# 11-CPU_GPIO.net
KiCad netlist of a schematic drawn in Altium Designer
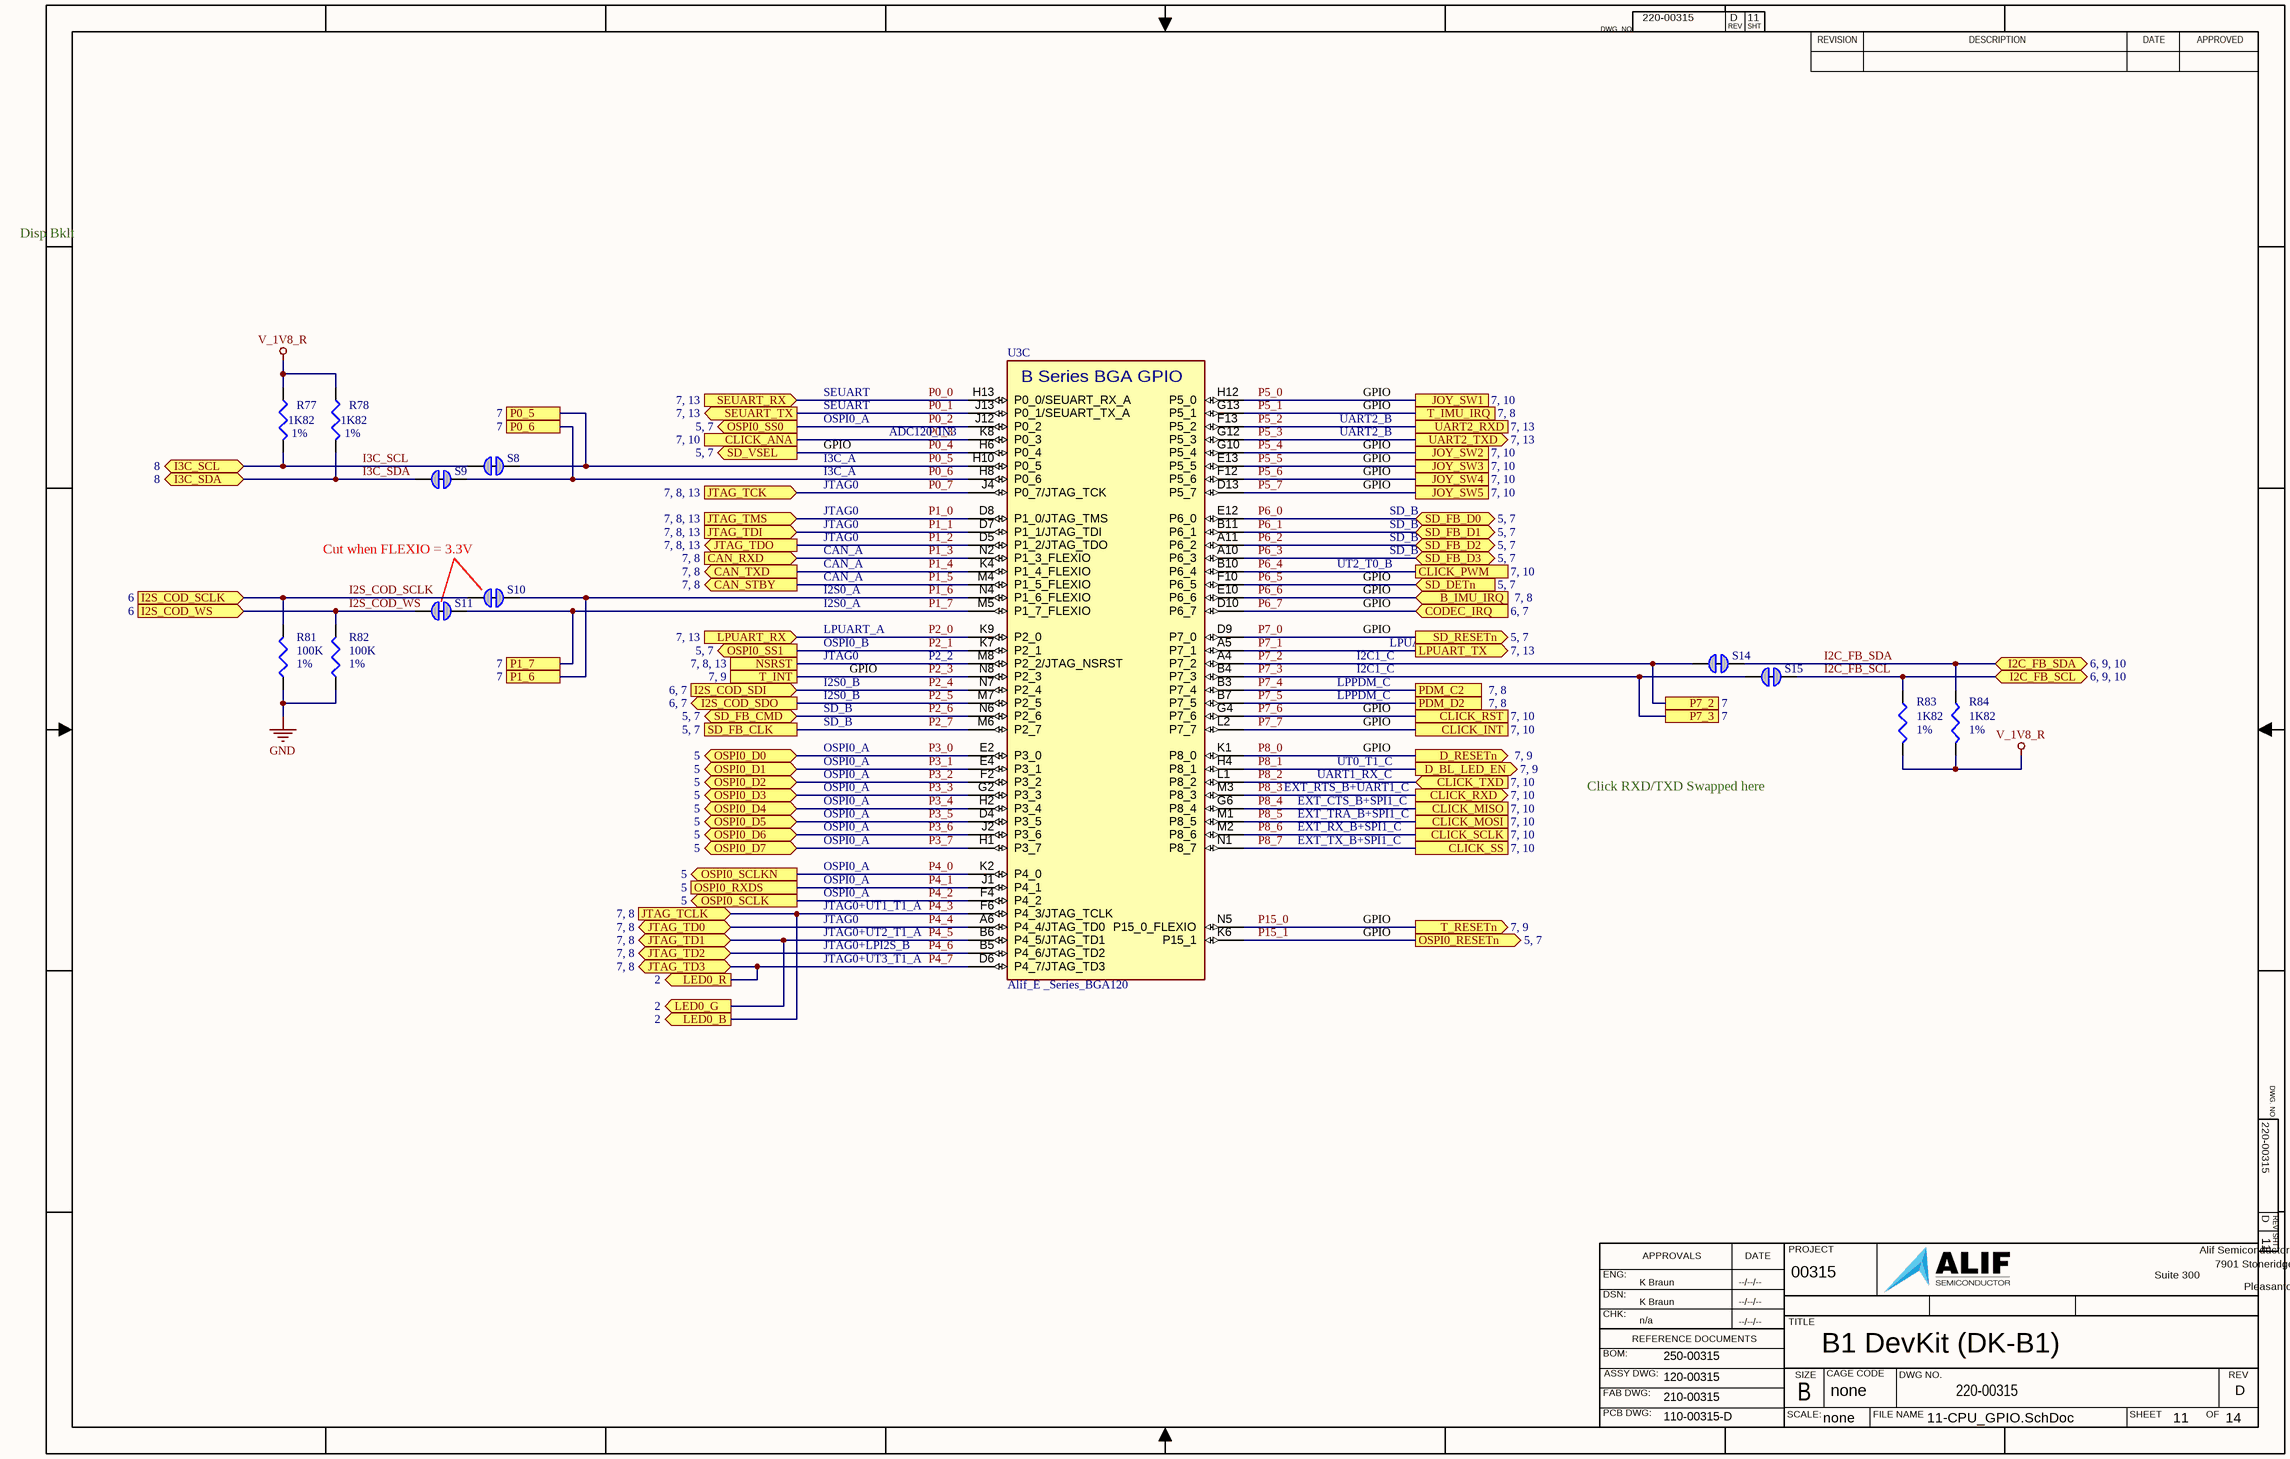
[diagram p0: 11-CPU_GPIO.SchDoc]

(export (version "E")
  (design (tool "Eeschema 10.0.6"))
  (components
    (comp (ref "R77")
      (value "1K82")
      (footprint "RESC0402-01")
      (description "Res,1K82,1%,100ppm,0402")
      (fields
        (field (name "TOLERANCE") "1%")
        (field (name "Comment") "Res3")
        (field (name "PUBLISHER") "Altium Limited")
      )
      (libsource (lib "kb1") (part "Res3"))
    )
    (comp (ref "R78")
      (value "1K82")
      (footprint "RESC0402-01")
      (description "Res,1K82,1%,100ppm,0402")
      (fields
        (field (name "TOLERANCE") "1%")
        (field (name "Comment") "Res3")
        (field (name "PUBLISHER") "Altium Limited")
      )
      (libsource (lib "kb1") (part "Res3"))
    )
    (comp (ref "R81")
      (value "100K")
      (footprint "RESC0402-01")
      (description "Res,100K,1%,100ppm,0402")
      (fields
        (field (name "TOLERANCE") "1%")
        (field (name "Comment") "Res3")
        (field (name "PUBLISHER") "Altium Limited")
      )
      (libsource (lib "kb1") (part "Res3"))
    )
    (comp (ref "R82")
      (value "100K")
      (footprint "RESC0402-01")
      (description "Res,100K,1%,100ppm,0402")
      (fields
        (field (name "TOLERANCE") "1%")
        (field (name "Comment") "Res3")
        (field (name "PUBLISHER") "Altium Limited")
      )
      (libsource (lib "kb1") (part "Res3"))
    )
    (comp (ref "R83")
      (value "1K82")
      (footprint "RESC0402-01")
      (description "Res,1K82,1%,100ppm,0402")
      (fields
        (field (name "TOLERANCE") "1%")
        (field (name "Comment") "Res3")
        (field (name "PUBLISHER") "Altium Limited")
      )
      (libsource (lib "kb1") (part "Res3"))
    )
    (comp (ref "R84")
      (value "1K82")
      (footprint "RESC0402-01")
      (description "Res,1K82,1%,100ppm,0402")
      (fields
        (field (name "TOLERANCE") "1%")
        (field (name "Comment") "Res3")
        (field (name "PUBLISHER") "Altium Limited")
      )
      (libsource (lib "kb1") (part "Res3"))
    )
    (comp (ref "S8")
      (value "SolderJumperShorted_Small")
      (footprint "Solderbridge_Shorted")
      (description "DNI,Solderable Jumper,Shorted")
      (fields (field (name "PUBLISHER") "Altium Limited"))
      (libsource (lib "Alif-2") (part "SolderJumperShorted_Small"))
    )
    (comp (ref "S9")
      (value "SolderJumperShorted_Small")
      (footprint "Solderbridge_Shorted")
      (description "DNI,Solderable Jumper,Shorted")
      (fields (field (name "PUBLISHER") "Altium Limited"))
      (libsource (lib "Alif-2") (part "SolderJumperShorted_Small"))
    )
    (comp (ref "S10")
      (value "SolderJumperShorted_Small")
      (footprint "Solderbridge_Shorted")
      (description "DNI,Solderable Jumper,Shorted")
      (fields (field (name "PUBLISHER") "Altium Limited"))
      (libsource (lib "Alif-2") (part "SolderJumperShorted_Small"))
    )
    (comp (ref "S11")
      (value "SolderJumperShorted_Small")
      (footprint "Solderbridge_Shorted")
      (description "DNI,Solderable Jumper,Shorted")
      (fields (field (name "PUBLISHER") "Altium Limited"))
      (libsource (lib "Alif-2") (part "SolderJumperShorted_Small"))
    )
    (comp (ref "S14")
      (value "SolderJumperShorted_Small")
      (footprint "Solderbridge_Shorted")
      (description "DNI,Solderable Jumper,Shorted")
      (fields (field (name "PUBLISHER") "Altium Limited"))
      (libsource (lib "") (part "SolderJumperShorted_Small_1"))
    )
    (comp (ref "S15")
      (value "SolderJumperShorted_Small")
      (footprint "Solderbridge_Shorted")
      (description "DNI,Solderable Jumper,Shorted")
      (fields (field (name "PUBLISHER") "Altium Limited"))
      (libsource (lib "") (part "SolderJumperShorted_Small_1"))
    )
    (comp (ref "U3")
      (value "Alif_E _Series_BGA120")
      (footprint "BGA120_socket-NO_SOCK_3D")
      (description "IC,Alif Spark B1 MCU, Rev A5 silicon,BGA120")
      (libsource (lib "Alif") (part "SPARK_B1_120BGA_A5"))
    )
  )
  (nets
    (net (code "1") (name "/I2C_FB_SCL") (class "Default")
      (node (ref "R83") (pin "1") (pinfunction "1_1") (pintype "passive"))
      (node (ref "S15") (pin "1") (pinfunction "1_1") (pintype "passive"))
    )
    (net (code "2") (name "/I2C_FB_SDA") (class "Default")
      (node (ref "R84") (pin "1") (pinfunction "1_1") (pintype "passive"))
      (node (ref "S14") (pin "1") (pinfunction "1_1") (pintype "passive"))
    )
    (net (code "3") (name "/I2S_COD_SCLK") (class "Default")
      (node (ref "R81") (pin "2") (pinfunction "2_2") (pintype "passive"))
      (node (ref "S10") (pin "1") (pinfunction "1_1") (pintype "passive"))
    )
    (net (code "4") (name "/I2S_COD_WS") (class "Default")
      (node (ref "R82") (pin "2") (pinfunction "2_2") (pintype "passive"))
      (node (ref "S11") (pin "1") (pinfunction "1_1") (pintype "passive"))
    )
    (net (code "5") (name "/I3C_SCL") (class "Default")
      (node (ref "R77") (pin "1") (pinfunction "1_1") (pintype "passive"))
      (node (ref "S8") (pin "1") (pinfunction "1_1") (pintype "passive"))
    )
    (net (code "6") (name "/I3C_SDA") (class "Default")
      (node (ref "R78") (pin "1") (pinfunction "1_1") (pintype "passive"))
      (node (ref "S9") (pin "1") (pinfunction "1_1") (pintype "passive"))
    )
    (net (code "7") (name "/NSRST") (class "Default")
      (node (ref "U3") (pin "M8") (pinfunction "P2_2/JTAG_NSRST_M8") (pintype "bidirectional"))
    )
    (net (code "8") (name "/P0_0") (class "Default")
      (node (ref "U3") (pin "H13") (pinfunction "P0_0/SEUART_RX_A_H13") (pintype "bidirectional"))
    )
    (net (code "9") (name "/P0_1") (class "Default")
      (node (ref "U3") (pin "J13") (pinfunction "P0_1/SEUART_TX_A_J13") (pintype "bidirectional"))
    )
    (net (code "10") (name "/P0_2") (class "Default")
      (node (ref "U3") (pin "J12") (pinfunction "P0_2_J12") (pintype "bidirectional"))
    )
    (net (code "11") (name "/P0_3") (class "Default")
      (node (ref "U3") (pin "K8") (pinfunction "P0_3_K8") (pintype "bidirectional"))
    )
    (net (code "12") (name "/P0_4") (class "Default")
      (node (ref "U3") (pin "H6") (pinfunction "P0_4_H6") (pintype "bidirectional"))
    )
    (net (code "13") (name "/P0_5") (class "Default")
      (node (ref "S8") (pin "2") (pinfunction "2_2") (pintype "passive"))
      (node (ref "U3") (pin "H10") (pinfunction "P0_5_H10") (pintype "bidirectional"))
    )
    (net (code "14") (name "/P0_6") (class "Default")
      (node (ref "S9") (pin "2") (pinfunction "2_2") (pintype "passive"))
      (node (ref "U3") (pin "H8") (pinfunction "P0_6_H8") (pintype "bidirectional"))
    )
    (net (code "15") (name "/P0_7") (class "Default")
      (node (ref "U3") (pin "J4") (pinfunction "P0_7/JTAG_TCK_J4") (pintype "bidirectional"))
    )
    (net (code "16") (name "/P1_0") (class "Default")
      (node (ref "U3") (pin "D8") (pinfunction "P1_0/JTAG_TMS_D8") (pintype "bidirectional"))
    )
    (net (code "17") (name "/P1_1") (class "Default")
      (node (ref "U3") (pin "D7") (pinfunction "P1_1/JTAG_TDI_D7") (pintype "bidirectional"))
    )
    (net (code "18") (name "/P1_2") (class "Default")
      (node (ref "U3") (pin "D5") (pinfunction "P1_2/JTAG_TDO_D5") (pintype "bidirectional"))
    )
    (net (code "19") (name "/P1_3") (class "Default")
      (node (ref "U3") (pin "N2") (pinfunction "P1_3_FLEXIO_N2") (pintype "bidirectional"))
    )
    (net (code "20") (name "/P1_4") (class "Default")
      (node (ref "U3") (pin "K4") (pinfunction "P1_4_FLEXIO_K4") (pintype "bidirectional"))
    )
    (net (code "21") (name "/P1_5") (class "Default")
      (node (ref "U3") (pin "M4") (pinfunction "P1_5_FLEXIO_M4") (pintype "bidirectional"))
    )
    (net (code "22") (name "/P1_6") (class "Default")
      (node (ref "S10") (pin "2") (pinfunction "2_2") (pintype "passive"))
      (node (ref "U3") (pin "N4") (pinfunction "P1_6_FLEXIO_N4") (pintype "bidirectional"))
    )
    (net (code "23") (name "/P1_7") (class "Default")
      (node (ref "S11") (pin "2") (pinfunction "2_2") (pintype "passive"))
      (node (ref "U3") (pin "M5") (pinfunction "P1_7_FLEXIO_M5") (pintype "bidirectional"))
    )
    (net (code "24") (name "/P2_0") (class "Default")
      (node (ref "U3") (pin "K9") (pinfunction "P2_0_K9") (pintype "bidirectional"))
    )
    (net (code "25") (name "/P2_1") (class "Default")
      (node (ref "U3") (pin "K7") (pinfunction "P2_1_K7") (pintype "bidirectional"))
    )
    (net (code "26") (name "/P2_3") (class "Default")
      (node (ref "U3") (pin "N8") (pinfunction "P2_3_N8") (pintype "bidirectional"))
    )
    (net (code "27") (name "/P2_4") (class "Default")
      (node (ref "U3") (pin "N7") (pinfunction "P2_4_N7") (pintype "bidirectional"))
    )
    (net (code "28") (name "/P2_5") (class "Default")
      (node (ref "U3") (pin "M7") (pinfunction "P2_5_M7") (pintype "bidirectional"))
    )
    (net (code "29") (name "/P2_6") (class "Default")
      (node (ref "U3") (pin "N6") (pinfunction "P2_6_N6") (pintype "bidirectional"))
    )
    (net (code "30") (name "/P2_7") (class "Default")
      (node (ref "U3") (pin "M6") (pinfunction "P2_7_M6") (pintype "bidirectional"))
    )
    (net (code "31") (name "/P3_0") (class "Default")
      (node (ref "U3") (pin "E2") (pinfunction "P3_0_E2") (pintype "bidirectional"))
    )
    (net (code "32") (name "/P3_1") (class "Default")
      (node (ref "U3") (pin "E4") (pinfunction "P3_1_E4") (pintype "bidirectional"))
    )
    (net (code "33") (name "/P3_2") (class "Default")
      (node (ref "U3") (pin "F2") (pinfunction "P3_2_F2") (pintype "bidirectional"))
    )
    (net (code "34") (name "/P3_3") (class "Default")
      (node (ref "U3") (pin "G2") (pinfunction "P3_3_G2") (pintype "bidirectional"))
    )
    (net (code "35") (name "/P3_4") (class "Default")
      (node (ref "U3") (pin "H2") (pinfunction "P3_4_H2") (pintype "bidirectional"))
    )
    (net (code "36") (name "/P3_5") (class "Default")
      (node (ref "U3") (pin "D4") (pinfunction "P3_5_D4") (pintype "bidirectional"))
    )
    (net (code "37") (name "/P3_6") (class "Default")
      (node (ref "U3") (pin "J2") (pinfunction "P3_6_J2") (pintype "bidirectional"))
    )
    (net (code "38") (name "/P3_7") (class "Default")
      (node (ref "U3") (pin "H1") (pinfunction "P3_7_H1") (pintype "bidirectional"))
    )
    (net (code "39") (name "/P4_0") (class "Default")
      (node (ref "U3") (pin "K2") (pinfunction "P4_0_K2") (pintype "bidirectional"))
    )
    (net (code "40") (name "/P4_1") (class "Default")
      (node (ref "U3") (pin "J1") (pinfunction "P4_1_J1") (pintype "bidirectional"))
    )
    (net (code "41") (name "/P4_2") (class "Default")
      (node (ref "U3") (pin "F4") (pinfunction "P4_2_F4") (pintype "bidirectional"))
    )
    (net (code "42") (name "/P4_3") (class "Default")
      (node (ref "U3") (pin "F6") (pinfunction "P4_3/JTAG_TCLK_F6") (pintype "bidirectional"))
    )
    (net (code "43") (name "/P4_4") (class "Default")
      (node (ref "U3") (pin "A6") (pinfunction "P4_4/JTAG_TD0_A6") (pintype "bidirectional"))
    )
    (net (code "44") (name "/P4_5") (class "Default")
      (node (ref "U3") (pin "B6") (pinfunction "P4_5/JTAG_TD1_B6") (pintype "bidirectional"))
    )
    (net (code "45") (name "/P4_6") (class "Default")
      (node (ref "U3") (pin "B5") (pinfunction "P4_6/JTAG_TD2_B5") (pintype "bidirectional"))
    )
    (net (code "46") (name "/P4_7") (class "Default")
      (node (ref "U3") (pin "D6") (pinfunction "P4_7/JTAG_TD3_D6") (pintype "bidirectional"))
    )
    (net (code "47") (name "/P5_0") (class "Default")
      (node (ref "U3") (pin "H12") (pinfunction "P5_0_H12") (pintype "bidirectional"))
    )
    (net (code "48") (name "/P5_1") (class "Default")
      (node (ref "U3") (pin "G13") (pinfunction "P5_1_G13") (pintype "bidirectional"))
    )
    (net (code "49") (name "/P5_2") (class "Default")
      (node (ref "U3") (pin "F13") (pinfunction "P5_2_F13") (pintype "bidirectional"))
    )
    (net (code "50") (name "/P5_3") (class "Default")
      (node (ref "U3") (pin "G12") (pinfunction "P5_3_G12") (pintype "bidirectional"))
    )
    (net (code "51") (name "/P5_4") (class "Default")
      (node (ref "U3") (pin "G10") (pinfunction "P5_4_G10") (pintype "bidirectional"))
    )
    (net (code "52") (name "/P5_5") (class "Default")
      (node (ref "U3") (pin "E13") (pinfunction "P5_5_E13") (pintype "bidirectional"))
    )
    (net (code "53") (name "/P5_6") (class "Default")
      (node (ref "U3") (pin "F12") (pinfunction "P5_6_F12") (pintype "bidirectional"))
    )
    (net (code "54") (name "/P5_7") (class "Default")
      (node (ref "U3") (pin "D13") (pinfunction "P5_7_D13") (pintype "bidirectional"))
    )
    (net (code "55") (name "/P6_0") (class "Default")
      (node (ref "U3") (pin "E12") (pinfunction "P6_0_E12") (pintype "bidirectional"))
    )
    (net (code "56") (name "/P6_1") (class "Default")
      (node (ref "U3") (pin "B11") (pinfunction "P6_1_B11") (pintype "bidirectional"))
    )
    (net (code "57") (name "/P6_2") (class "Default")
      (node (ref "U3") (pin "A11") (pinfunction "P6_2_A11") (pintype "bidirectional"))
    )
    (net (code "58") (name "/P6_3") (class "Default")
      (node (ref "U3") (pin "A10") (pinfunction "P6_3_A10") (pintype "bidirectional"))
    )
    (net (code "59") (name "/P6_4") (class "Default")
      (node (ref "U3") (pin "B10") (pinfunction "P6_4_B10") (pintype "bidirectional"))
    )
    (net (code "60") (name "/P6_5") (class "Default")
      (node (ref "U3") (pin "F10") (pinfunction "P6_5_F10") (pintype "bidirectional"))
    )
    (net (code "61") (name "/P6_6") (class "Default")
      (node (ref "U3") (pin "E10") (pinfunction "P6_6_E10") (pintype "bidirectional"))
    )
    (net (code "62") (name "/P6_7") (class "Default")
      (node (ref "U3") (pin "D10") (pinfunction "P6_7_D10") (pintype "bidirectional"))
    )
    (net (code "63") (name "/P7_0") (class "Default")
      (node (ref "U3") (pin "D9") (pinfunction "P7_0_D9") (pintype "bidirectional"))
    )
    (net (code "64") (name "/P7_1") (class "Default")
      (node (ref "U3") (pin "A5") (pinfunction "P7_1_A5") (pintype "bidirectional"))
    )
    (net (code "65") (name "/P7_2") (class "Default")
      (node (ref "S14") (pin "2") (pinfunction "2_2") (pintype "passive"))
      (node (ref "U3") (pin "A4") (pinfunction "P7_2_A4") (pintype "bidirectional"))
    )
    (net (code "66") (name "/P7_3") (class "Default")
      (node (ref "S15") (pin "2") (pinfunction "2_2") (pintype "passive"))
      (node (ref "U3") (pin "B4") (pinfunction "P7_3_B4") (pintype "bidirectional"))
    )
    (net (code "67") (name "/P7_4") (class "Default")
      (node (ref "U3") (pin "B3") (pinfunction "P7_4_B3") (pintype "bidirectional"))
    )
    (net (code "68") (name "/P7_5") (class "Default")
      (node (ref "U3") (pin "B7") (pinfunction "P7_5_B7") (pintype "bidirectional"))
    )
    (net (code "69") (name "/P7_6") (class "Default")
      (node (ref "U3") (pin "G4") (pinfunction "P7_6_G4") (pintype "bidirectional"))
    )
    (net (code "70") (name "/P7_7") (class "Default")
      (node (ref "U3") (pin "L2") (pinfunction "P7_7_L2") (pintype "bidirectional"))
    )
    (net (code "71") (name "/P8_0") (class "Default")
      (node (ref "U3") (pin "K1") (pinfunction "P8_0_K1") (pintype "bidirectional"))
    )
    (net (code "72") (name "/P8_1") (class "Default")
      (node (ref "U3") (pin "H4") (pinfunction "P8_1_H4") (pintype "bidirectional"))
    )
    (net (code "73") (name "/P8_2") (class "Default")
      (node (ref "U3") (pin "L1") (pinfunction "P8_2_L1") (pintype "bidirectional"))
    )
    (net (code "74") (name "/P8_3") (class "Default")
      (node (ref "U3") (pin "M3") (pinfunction "P8_3_M3") (pintype "bidirectional"))
    )
    (net (code "75") (name "/P8_4") (class "Default")
      (node (ref "U3") (pin "G6") (pinfunction "P8_4_G6") (pintype "bidirectional"))
    )
    (net (code "76") (name "/P8_5") (class "Default")
      (node (ref "U3") (pin "M1") (pinfunction "P8_5_M1") (pintype "bidirectional"))
    )
    (net (code "77") (name "/P8_6") (class "Default")
      (node (ref "U3") (pin "M2") (pinfunction "P8_6_M2") (pintype "bidirectional"))
    )
    (net (code "78") (name "/P8_7") (class "Default")
      (node (ref "U3") (pin "N1") (pinfunction "P8_7_N1") (pintype "bidirectional"))
    )
    (net (code "79") (name "/P15_0") (class "Default")
      (node (ref "U3") (pin "N5") (pinfunction "P15_0_FLEXIO_N5") (pintype "bidirectional"))
    )
    (net (code "80") (name "/P15_1") (class "Default")
      (node (ref "U3") (pin "K6") (pinfunction "P15_1_K6") (pintype "bidirectional"))
    )
    (net (code "81") (name "GND") (class "Default")
      (node (ref "R81") (pin "1") (pinfunction "1_1") (pintype "passive"))
      (node (ref "R82") (pin "1") (pinfunction "1_1") (pintype "passive"))
    )
    (net (code "82") (name "V_1V8_R") (class "Default")
      (node (ref "R77") (pin "2") (pinfunction "2_2") (pintype "passive"))
      (node (ref "R78") (pin "2") (pinfunction "2_2") (pintype "passive"))
      (node (ref "R83") (pin "2") (pinfunction "2_2") (pintype "passive"))
      (node (ref "R84") (pin "2") (pinfunction "2_2") (pintype "passive"))
    )
  )
)
